# echo-we.net
KiCad netlist of a schematic drawn in EAGLE
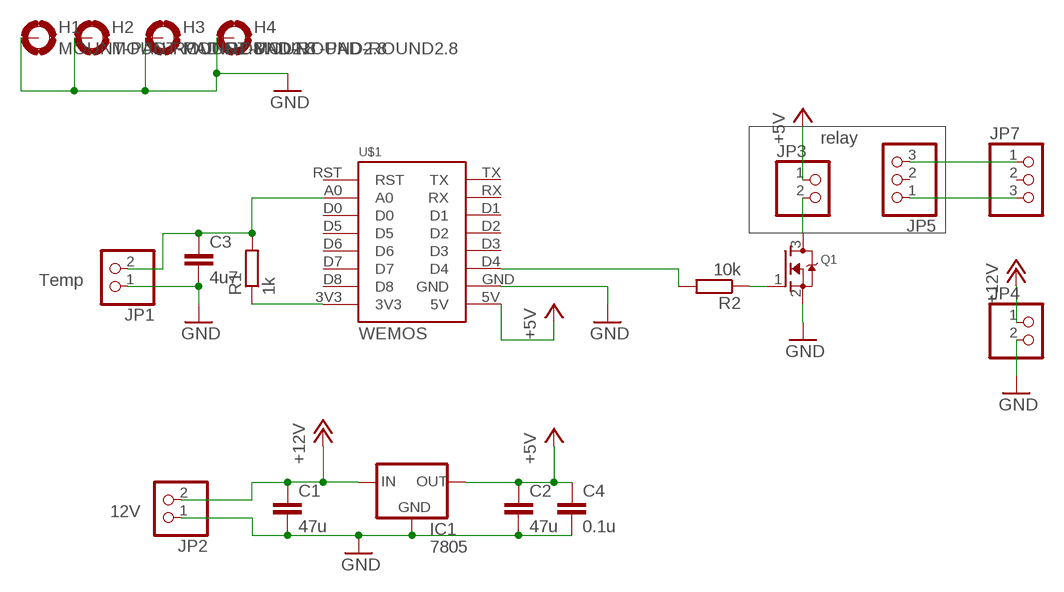
[diagram p0: schematic, sheet 1]

(export (version "E")
  (design (tool "Eeschema 10.0.6"))
  (components
    (comp (ref "C1")
      (value "47u")
      (footprint "eagle-import:C1206")
      (libsource (lib "eagle-import") (part "C-EUC1206"))
    )
    (comp (ref "C2")
      (value "47u")
      (footprint "eagle-import:C1206")
      (libsource (lib "eagle-import") (part "C-EUC1206"))
    )
    (comp (ref "C3")
      (value "4u7")
      (footprint "eagle-import:C1206")
      (libsource (lib "eagle-import") (part "C-EUC1206"))
    )
    (comp (ref "C4")
      (value "0.1u")
      (footprint "eagle-import:C1206")
      (libsource (lib "eagle-import") (part "C-EUC1206"))
    )
    (comp (ref "H1")
      (value "MOUNT-PAD-ROUND2.8")
      (footprint "eagle-import:2,8-PAD")
      (libsource (lib "eagle-import") (part "MOUNT-PAD-ROUND2.8"))
    )
    (comp (ref "H2")
      (value "MOUNT-PAD-ROUND2.8")
      (footprint "eagle-import:2,8-PAD")
      (libsource (lib "eagle-import") (part "MOUNT-PAD-ROUND2.8"))
    )
    (comp (ref "H3")
      (value "MOUNT-PAD-ROUND2.8")
      (footprint "eagle-import:2,8-PAD")
      (libsource (lib "eagle-import") (part "MOUNT-PAD-ROUND2.8"))
    )
    (comp (ref "H4")
      (value "MOUNT-PAD-ROUND2.8")
      (footprint "eagle-import:2,8-PAD")
      (libsource (lib "eagle-import") (part "MOUNT-PAD-ROUND2.8"))
    )
    (comp (ref "IC1")
      (value "7805")
      (footprint "eagle-import:78XXS")
      (libsource (lib "eagle-import") (part "78XXS"))
    )
    (comp (ref "JP1")
      (value "PINHD-1X2")
      (footprint "eagle-import:1X02")
      (libsource (lib "eagle-import") (part "PINHD-1X2"))
    )
    (comp (ref "JP2")
      (value "PINHD-1X2")
      (footprint "eagle-import:1X02")
      (libsource (lib "eagle-import") (part "PINHD-1X2"))
    )
    (comp (ref "JP3")
      (value "PINHD-1X2")
      (footprint "eagle-import:1X02")
      (libsource (lib "eagle-import") (part "PINHD-1X2"))
    )
    (comp (ref "JP4")
      (value "PINHD-1X2")
      (footprint "eagle-import:1X02")
      (libsource (lib "eagle-import") (part "PINHD-1X2"))
    )
    (comp (ref "JP5")
      (value "PINHD-1X3")
      (footprint "eagle-import:1X03")
      (libsource (lib "eagle-import") (part "PINHD-1X3"))
    )
    (comp (ref "JP7")
      (value "PINHD-1X3")
      (footprint "eagle-import:1X03")
      (libsource (lib "eagle-import") (part "PINHD-1X3"))
    )
    (comp (ref "Q1")
      (value "MOSFET-NREFLOW")
      (footprint "eagle-import:SOT23")
      (libsource (lib "eagle-import") (part "MOSFET-NREFLOW"))
    )
    (comp (ref "R1")
      (value "1k")
      (footprint "eagle-import:R0805")
      (libsource (lib "eagle-import") (part "R-EU_R0805"))
    )
    (comp (ref "R2")
      (value "10k")
      (footprint "eagle-import:R0805")
      (libsource (lib "eagle-import") (part "R-EU_R0805"))
    )
    (comp (ref "U$1")
      (value "WEMOS")
      (footprint "eagle-import:WEMOS")
      (libsource (lib "eagle-import") (part "WEMOS"))
    )
  )
  (nets
    (net (code "1") (name "+5V") (class "Default")
      (node (ref "C2") (pin "1") (pinfunction "1_1") (pintype "passive"))
      (node (ref "C4") (pin "1") (pinfunction "1_1") (pintype "passive"))
      (node (ref "IC1") (pin "OUT") (pinfunction "OUT_OUT") (pintype "passive"))
      (node (ref "JP3") (pin "1") (pinfunction "1_1") (pintype "passive"))
      (node (ref "U$1") (pin "5V") (pinfunction "5V_5V") (pintype "bidirectional"))
    )
    (net (code "2") (name "+12V") (class "Default")
      (node (ref "C1") (pin "1") (pinfunction "1_1") (pintype "passive"))
      (node (ref "IC1") (pin "IN") (pinfunction "IN_IN") (pintype "input"))
      (node (ref "JP2") (pin "2") (pinfunction "2_2") (pintype "passive"))
      (node (ref "JP4") (pin "1") (pinfunction "1_1") (pintype "passive"))
    )
    (net (code "3") (name "GND") (class "Default")
      (node (ref "C1") (pin "2") (pinfunction "2_2") (pintype "passive"))
      (node (ref "C2") (pin "2") (pinfunction "2_2") (pintype "passive"))
      (node (ref "C3") (pin "2") (pinfunction "2_2") (pintype "passive"))
      (node (ref "C4") (pin "2") (pinfunction "2_2") (pintype "passive"))
      (node (ref "H1") (pin "B2,8") (pinfunction "MOUNT_B2,8") (pintype "passive"))
      (node (ref "H2") (pin "B2,8") (pinfunction "MOUNT_B2,8") (pintype "passive"))
      (node (ref "H3") (pin "B2,8") (pinfunction "MOUNT_B2,8") (pintype "passive"))
      (node (ref "H4") (pin "B2,8") (pinfunction "MOUNT_B2,8") (pintype "passive"))
      (node (ref "IC1") (pin "GND") (pinfunction "GND_GND") (pintype "input"))
      (node (ref "JP1") (pin "1") (pinfunction "1_1") (pintype "passive"))
      (node (ref "JP2") (pin "1") (pinfunction "1_1") (pintype "passive"))
      (node (ref "JP4") (pin "2") (pinfunction "2_2") (pintype "passive"))
      (node (ref "Q1") (pin "2") (pinfunction "S_2") (pintype "bidirectional"))
      (node (ref "U$1") (pin "GND") (pinfunction "GND_GND") (pintype "bidirectional"))
    )
    (net (code "4") (name "Net-(C3-Pad1)") (class "Default")
      (node (ref "C3") (pin "1") (pinfunction "1_1") (pintype "passive"))
      (node (ref "JP1") (pin "2") (pinfunction "2_2") (pintype "passive"))
      (node (ref "R1") (pin "2") (pinfunction "2_2") (pintype "passive"))
      (node (ref "U$1") (pin "A0") (pinfunction "A0_A0") (pintype "bidirectional"))
    )
    (net (code "5") (name "Net-(JP5-Pad1)") (class "Default")
      (node (ref "JP5") (pin "1") (pinfunction "1_1") (pintype "passive"))
      (node (ref "JP7") (pin "3") (pinfunction "3_3") (pintype "passive"))
    )
    (net (code "6") (name "Net-(JP5-Pad3)") (class "Default")
      (node (ref "JP5") (pin "3") (pinfunction "3_3") (pintype "passive"))
      (node (ref "JP7") (pin "1") (pinfunction "1_1") (pintype "passive"))
    )
    (net (code "7") (name "Net-(Q1-D)") (class "Default")
      (node (ref "JP3") (pin "2") (pinfunction "2_2") (pintype "passive"))
      (node (ref "Q1") (pin "3") (pinfunction "D_3") (pintype "bidirectional"))
    )
    (net (code "8") (name "Net-(Q1-G)") (class "Default")
      (node (ref "Q1") (pin "1") (pinfunction "G_1") (pintype "bidirectional"))
      (node (ref "R2") (pin "1") (pinfunction "1_1") (pintype "passive"))
    )
    (net (code "9") (name "Net-(R1-Pad1)") (class "Default")
      (node (ref "R1") (pin "1") (pinfunction "1_1") (pintype "passive"))
      (node (ref "U$1") (pin "3V3") (pinfunction "3V3_3V3") (pintype "bidirectional"))
    )
    (net (code "10") (name "Net-(R2-Pad2)") (class "Default")
      (node (ref "R2") (pin "2") (pinfunction "2_2") (pintype "passive"))
      (node (ref "U$1") (pin "D4") (pinfunction "D4_D4") (pintype "bidirectional"))
    )
    (net (code "11") (name "unconnected-(JP5-Pad2)") (class "Default")
      (node (ref "JP5") (pin "2") (pinfunction "2_2") (pintype "passive"))
    )
    (net (code "12") (name "unconnected-(JP7-Pad2)") (class "Default")
      (node (ref "JP7") (pin "2") (pinfunction "2_2") (pintype "passive"))
    )
    (net (code "13") (name "unconnected-(U$1-PadD0)") (class "Default")
      (node (ref "U$1") (pin "D0") (pinfunction "D0_D0") (pintype "bidirectional"))
    )
    (net (code "14") (name "unconnected-(U$1-PadD1)") (class "Default")
      (node (ref "U$1") (pin "D1") (pinfunction "D1_D1") (pintype "bidirectional"))
    )
    (net (code "15") (name "unconnected-(U$1-PadD2)") (class "Default")
      (node (ref "U$1") (pin "D2") (pinfunction "D2_D2") (pintype "bidirectional"))
    )
    (net (code "16") (name "unconnected-(U$1-PadD3)") (class "Default")
      (node (ref "U$1") (pin "D3") (pinfunction "D3_D3") (pintype "bidirectional"))
    )
    (net (code "17") (name "unconnected-(U$1-PadD5)") (class "Default")
      (node (ref "U$1") (pin "D5") (pinfunction "D5_D5") (pintype "bidirectional"))
    )
    (net (code "18") (name "unconnected-(U$1-PadD6)") (class "Default")
      (node (ref "U$1") (pin "D6") (pinfunction "D6_D6") (pintype "bidirectional"))
    )
    (net (code "19") (name "unconnected-(U$1-PadD7)") (class "Default")
      (node (ref "U$1") (pin "D7") (pinfunction "D7_D7") (pintype "bidirectional"))
    )
    (net (code "20") (name "unconnected-(U$1-PadD8)") (class "Default")
      (node (ref "U$1") (pin "D8") (pinfunction "D8_D8") (pintype "bidirectional"))
    )
    (net (code "21") (name "unconnected-(U$1-PadRST)") (class "Default")
      (node (ref "U$1") (pin "RST") (pinfunction "RST_RST") (pintype "bidirectional"))
    )
    (net (code "22") (name "unconnected-(U$1-PadRX)") (class "Default")
      (node (ref "U$1") (pin "RX") (pinfunction "RX_RX") (pintype "bidirectional"))
    )
    (net (code "23") (name "unconnected-(U$1-PadTX)") (class "Default")
      (node (ref "U$1") (pin "TX") (pinfunction "TX_TX") (pintype "bidirectional"))
    )
  )
)
